# Grove_-_Mini_I2C_Motor_Driver_v1_0.net
KiCad netlist of a schematic drawn in EAGLE
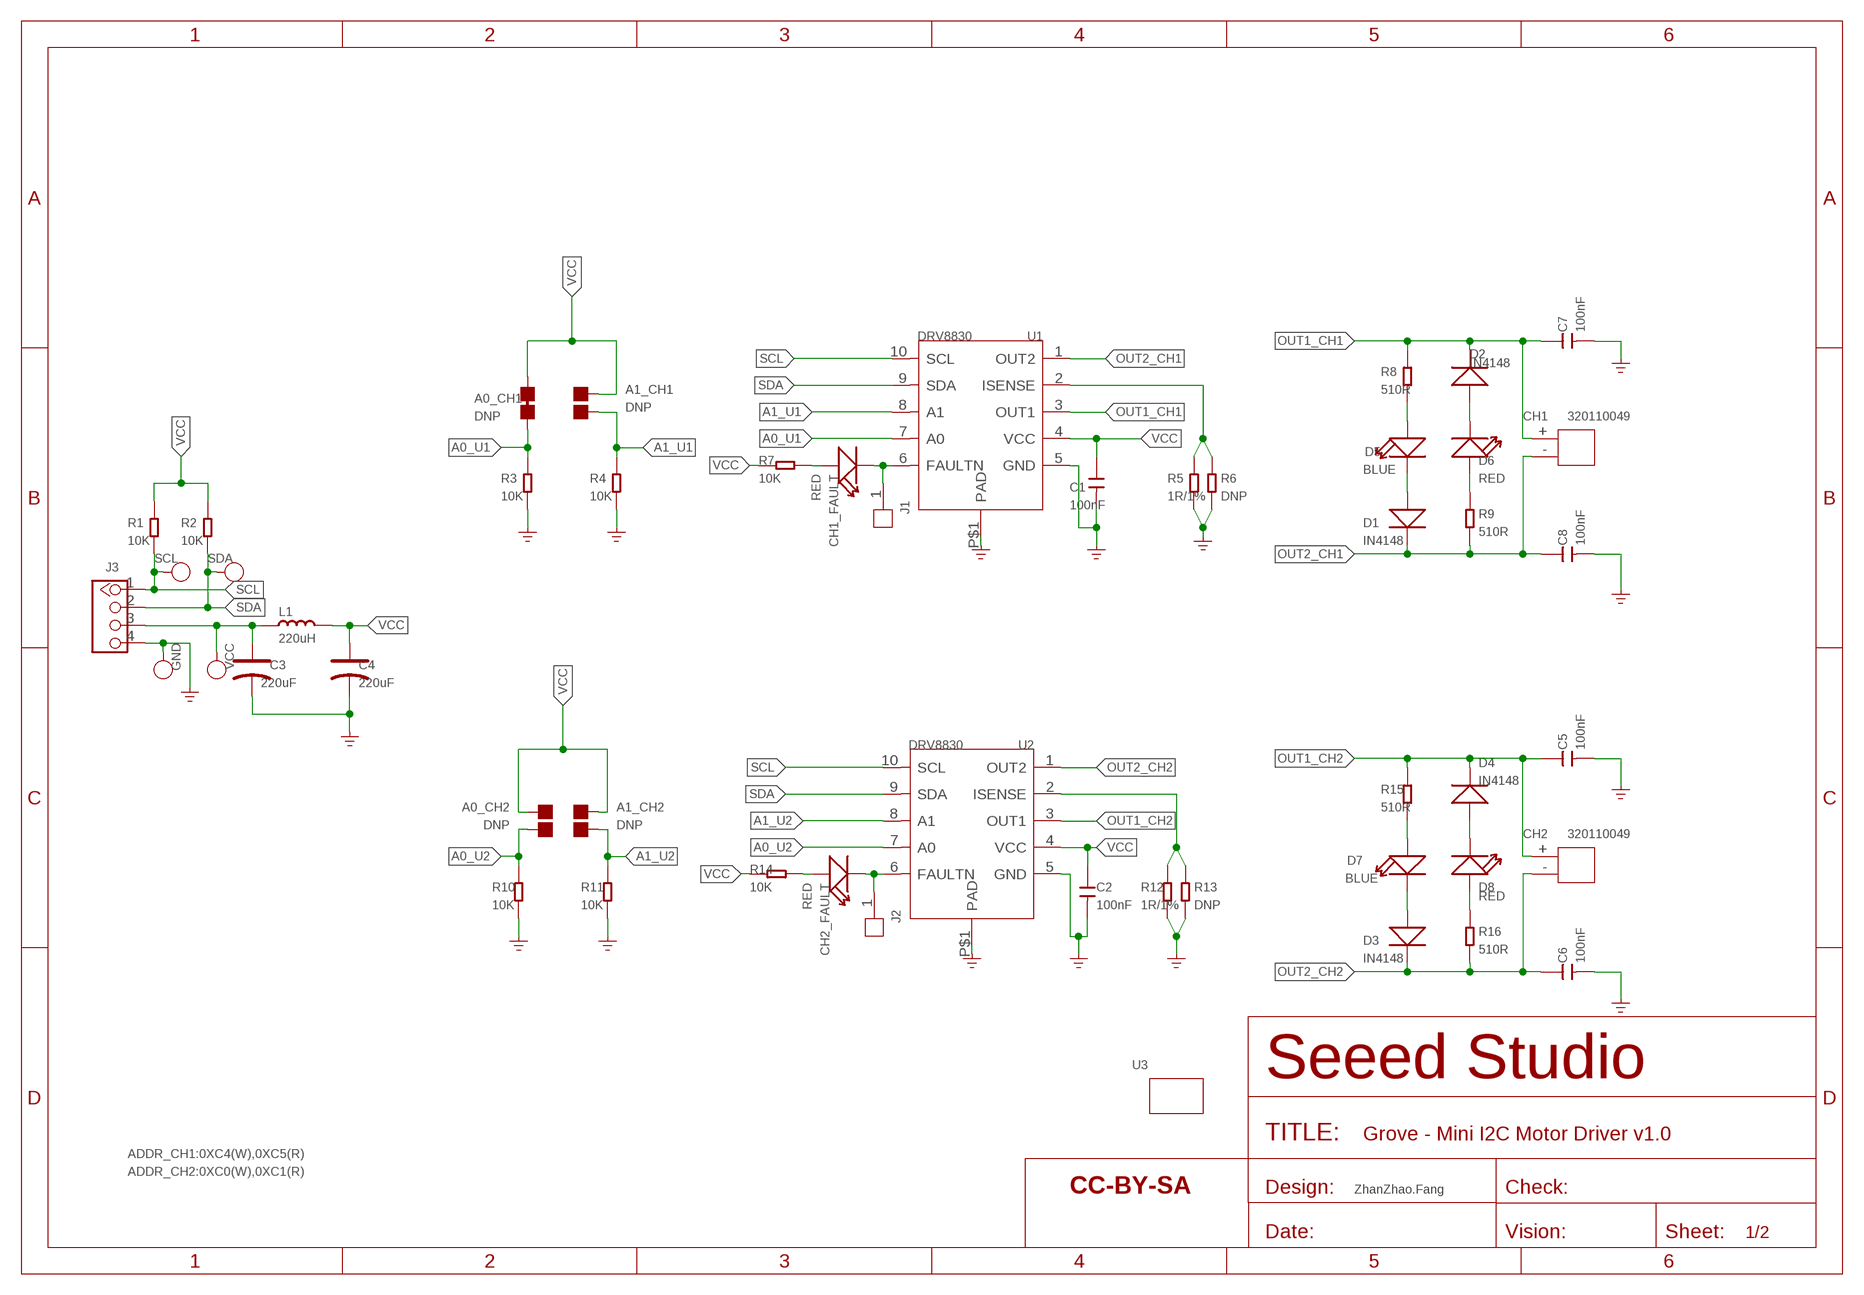
[diagram p0: schematic, sheet 1]

(export (version "E")
  (design (tool "Eeschema 10.0.6"))
  (components
    (comp (ref "A0_CH1")
      (value "DNP")
      (footprint "eagle-import:2P-SMD-SHORT")
      (libsource (lib "eagle-import") (part "JUMPER-2P-SHORT"))
    )
    (comp (ref "A0_CH2")
      (value "DNP")
      (footprint "eagle-import:JUMPER-2P")
      (libsource (lib "eagle-import") (part "JUMPER-2P"))
    )
    (comp (ref "A1_CH1")
      (value "DNP")
      (footprint "eagle-import:JUMPER-2P")
      (libsource (lib "eagle-import") (part "JUMPER-2P"))
    )
    (comp (ref "A1_CH2")
      (value "DNP")
      (footprint "eagle-import:JUMPER-2P")
      (libsource (lib "eagle-import") (part "JUMPER-2P"))
    )
    (comp (ref "C1")
      (value "100nF")
      (footprint "eagle-import:C0603")
      (libsource (lib "eagle-import") (part "CAP-0603"))
    )
    (comp (ref "C2")
      (value "100nF")
      (footprint "eagle-import:C0603")
      (libsource (lib "eagle-import") (part "CAP-0603"))
    )
    (comp (ref "C3")
      (value "220uF")
      (footprint "eagle-import:AVX-B")
      (libsource (lib "eagle-import") (part "CAP-POLAR-AVX-B"))
    )
    (comp (ref "C4")
      (value "220uF")
      (footprint "eagle-import:AVX-B")
      (libsource (lib "eagle-import") (part "CAP-POLAR-AVX-B"))
    )
    (comp (ref "C5")
      (value "100nF")
      (footprint "eagle-import:C0603")
      (libsource (lib "eagle-import") (part "CAP-0603"))
    )
    (comp (ref "C6")
      (value "100nF")
      (footprint "eagle-import:C0603")
      (libsource (lib "eagle-import") (part "CAP-0603"))
    )
    (comp (ref "C7")
      (value "100nF")
      (footprint "eagle-import:C0603")
      (libsource (lib "eagle-import") (part "CAP-0603"))
    )
    (comp (ref "C8")
      (value "100nF")
      (footprint "eagle-import:C0603")
      (libsource (lib "eagle-import") (part "CAP-0603"))
    )
    (comp (ref "CH1")
      (value "320110049")
      (footprint "eagle-import:H2-2.0-6X4.5MM")
      (libsource (lib "eagle-import") (part "JST-2P-DIP'2.0'"))
    )
    (comp (ref "CH1_FAULT")
      (value "RED")
      (footprint "eagle-import:LED-0603")
      (libsource (lib "eagle-import") (part "LED'0603'"))
    )
    (comp (ref "CH2")
      (value "320110049")
      (footprint "eagle-import:H2-2.0-6X4.5MM")
      (libsource (lib "eagle-import") (part "JST-2P-DIP'2.0'"))
    )
    (comp (ref "CH2_FAULT")
      (value "RED")
      (footprint "eagle-import:LED-0603")
      (libsource (lib "eagle-import") (part "LED'0603'"))
    )
    (comp (ref "D1")
      (value "IN4148")
      (footprint "eagle-import:SOD-323")
      (libsource (lib "eagle-import") (part "DIODE'0805'"))
    )
    (comp (ref "D2")
      (value "IN4148")
      (footprint "eagle-import:SOD-323")
      (libsource (lib "eagle-import") (part "DIODE'0805'"))
    )
    (comp (ref "D3")
      (value "IN4148")
      (footprint "eagle-import:SOD-323")
      (libsource (lib "eagle-import") (part "DIODE'0805'"))
    )
    (comp (ref "D4")
      (value "IN4148")
      (footprint "eagle-import:SOD-323")
      (libsource (lib "eagle-import") (part "DIODE'0805'"))
    )
    (comp (ref "D5")
      (value "BLUE")
      (footprint "eagle-import:LED-0603")
      (libsource (lib "eagle-import") (part "LED'0603'"))
    )
    (comp (ref "D6")
      (value "RED")
      (footprint "eagle-import:LED-0603")
      (libsource (lib "eagle-import") (part "LED'0603'"))
    )
    (comp (ref "D7")
      (value "BLUE")
      (footprint "eagle-import:LED-0603")
      (libsource (lib "eagle-import") (part "LED'0603'"))
    )
    (comp (ref "D8")
      (value "RED")
      (footprint "eagle-import:LED-0603")
      (libsource (lib "eagle-import") (part "LED'0603'"))
    )
    (comp (ref "GND")
      (value "DNP")
      (footprint "eagle-import:TP-D45MIL")
      (libsource (lib "eagle-import") (part "TEST-POINT'4545'"))
    )
    (comp (ref "J1")
      (value "HEADER-1P-40")
      (footprint "eagle-import:1P-80_40MIL")
      (libsource (lib "eagle-import") (part "HEADER-1P-40"))
    )
    (comp (ref "J2")
      (value "HEADER-1P-40")
      (footprint "eagle-import:1P-80_40MIL")
      (libsource (lib "eagle-import") (part "HEADER-1P-40"))
    )
    (comp (ref "J3")
      (value "GROVE-CONNECTOR-DIP-2.0")
      (footprint "eagle-import:HW4-2.0")
      (libsource (lib "eagle-import") (part "GROVE-CONNECTOR-DIP-2.0"))
    )
    (comp (ref "L1")
      (value "220uH")
      (footprint "eagle-import:INT2-SMD-4.8X4.8X3MM")
      (libsource (lib "eagle-import") (part "INDUCTOR/FERRITE-BEAD"))
    )
    (comp (ref "R1")
      (value "10K")
      (footprint "eagle-import:R0603")
      (libsource (lib "eagle-import") (part "RES-0603"))
    )
    (comp (ref "R2")
      (value "10K")
      (footprint "eagle-import:R0603")
      (libsource (lib "eagle-import") (part "RES-0603"))
    )
    (comp (ref "R3")
      (value "10K")
      (footprint "eagle-import:R0603")
      (libsource (lib "eagle-import") (part "RES-0603"))
    )
    (comp (ref "R4")
      (value "10K")
      (footprint "eagle-import:R0603")
      (libsource (lib "eagle-import") (part "RES-0603"))
    )
    (comp (ref "R5")
      (value "1R/1%")
      (footprint "eagle-import:R0603")
      (libsource (lib "eagle-import") (part "RES-0603"))
    )
    (comp (ref "R6")
      (value "DNP")
      (footprint "eagle-import:R0603")
      (libsource (lib "eagle-import") (part "RES-0603"))
    )
    (comp (ref "R7")
      (value "10K")
      (footprint "eagle-import:R0603")
      (libsource (lib "eagle-import") (part "RES-0603"))
    )
    (comp (ref "R8")
      (value "510R")
      (footprint "eagle-import:R0603")
      (libsource (lib "eagle-import") (part "RES-0603"))
    )
    (comp (ref "R9")
      (value "510R")
      (footprint "eagle-import:R0603")
      (libsource (lib "eagle-import") (part "RES-0603"))
    )
    (comp (ref "R10")
      (value "10K")
      (footprint "eagle-import:R0603")
      (libsource (lib "eagle-import") (part "RES-0603"))
    )
    (comp (ref "R11")
      (value "10K")
      (footprint "eagle-import:R0603")
      (libsource (lib "eagle-import") (part "RES-0603"))
    )
    (comp (ref "R12")
      (value "1R/1%")
      (footprint "eagle-import:R0603")
      (libsource (lib "eagle-import") (part "RES-0603"))
    )
    (comp (ref "R13")
      (value "DNP")
      (footprint "eagle-import:R0603")
      (libsource (lib "eagle-import") (part "RES-0603"))
    )
    (comp (ref "R14")
      (value "10K")
      (footprint "eagle-import:R0603")
      (libsource (lib "eagle-import") (part "RES-0603"))
    )
    (comp (ref "R15")
      (value "510R")
      (footprint "eagle-import:R0603")
      (libsource (lib "eagle-import") (part "RES-0603"))
    )
    (comp (ref "R16")
      (value "510R")
      (footprint "eagle-import:R0603")
      (libsource (lib "eagle-import") (part "RES-0603"))
    )
    (comp (ref "SCL")
      (value "DNP")
      (footprint "eagle-import:TP-D45MIL")
      (libsource (lib "eagle-import") (part "TEST-POINT'4545'"))
    )
    (comp (ref "SDA")
      (value "DNP")
      (footprint "eagle-import:TP-D45MIL")
      (libsource (lib "eagle-import") (part "TEST-POINT'4545'"))
    )
    (comp (ref "U$1")
      (value "SEEEDSTUDIO-OPEN-SCH-FRAME")
      (footprint "eagle-import:SEEEDSTUDIO-PCB-FRAME")
      (libsource (lib "eagle-import") (part "SEEEDSTUDIO-OPEN-SCH-FRAME"))
    )
    (comp (ref "U1")
      (value "DRV8830")
      (footprint "eagle-import:MSOP10-0.5-3X3MM")
      (libsource (lib "eagle-import") (part "DRIVER-DRV8830"))
    )
    (comp (ref "U2")
      (value "DRV8830")
      (footprint "eagle-import:MSOP10-0.5-3X3MM")
      (libsource (lib "eagle-import") (part "DRIVER-DRV8830"))
    )
    (comp (ref "U3")
      (value "GROVE'2U'")
      (footprint "eagle-import:GROVE-1_2-TEST-PLATFORM")
      (libsource (lib "eagle-import") (part "GROVE'2U'"))
    )
    (comp (ref "VCC")
      (value "DNP")
      (footprint "eagle-import:TP-D45MIL")
      (libsource (lib "eagle-import") (part "TEST-POINT'4545'"))
    )
  )
  (nets
    (net (code "1") (name "A0_U1") (class "Default")
      (node (ref "A0_CH1") (pin "1") (pinfunction "1_1") (pintype "bidirectional"))
      (node (ref "R3") (pin "2") (pinfunction "2_2") (pintype "passive"))
      (node (ref "U1") (pin "7") (pinfunction "A0_7") (pintype "bidirectional"))
    )
    (net (code "2") (name "A0_U2") (class "Default")
      (node (ref "A0_CH2") (pin "1") (pinfunction "1_1") (pintype "bidirectional"))
      (node (ref "R10") (pin "2") (pinfunction "2_2") (pintype "passive"))
      (node (ref "U2") (pin "7") (pinfunction "A0_7") (pintype "bidirectional"))
    )
    (net (code "3") (name "A1_U1") (class "Default")
      (node (ref "A1_CH1") (pin "1") (pinfunction "1_1") (pintype "bidirectional"))
      (node (ref "R4") (pin "2") (pinfunction "2_2") (pintype "passive"))
      (node (ref "U1") (pin "8") (pinfunction "A1_8") (pintype "bidirectional"))
    )
    (net (code "4") (name "A1_U2") (class "Default")
      (node (ref "A1_CH2") (pin "1") (pinfunction "1_1") (pintype "bidirectional"))
      (node (ref "R11") (pin "2") (pinfunction "2_2") (pintype "passive"))
      (node (ref "U2") (pin "8") (pinfunction "A1_8") (pintype "bidirectional"))
    )
    (net (code "5") (name "GND") (class "Default")
      (node (ref "C1") (pin "2") (pinfunction "2_2") (pintype "passive"))
      (node (ref "C2") (pin "2") (pinfunction "2_2") (pintype "passive"))
      (node (ref "C3") (pin "-") (pinfunction "-_-") (pintype "passive"))
      (node (ref "C4") (pin "-") (pinfunction "-_-") (pintype "passive"))
      (node (ref "C5") (pin "2") (pinfunction "2_2") (pintype "passive"))
      (node (ref "C6") (pin "2") (pinfunction "2_2") (pintype "passive"))
      (node (ref "C7") (pin "2") (pinfunction "2_2") (pintype "passive"))
      (node (ref "C8") (pin "2") (pinfunction "2_2") (pintype "passive"))
      (node (ref "GND") (pin "T") (pinfunction "T_T") (pintype "bidirectional"))
      (node (ref "J3") (pin "4") (pinfunction "4_4") (pintype "bidirectional"))
      (node (ref "R10") (pin "1") (pinfunction "1_1") (pintype "passive"))
      (node (ref "R11") (pin "1") (pinfunction "1_1") (pintype "passive"))
      (node (ref "R12") (pin "1") (pinfunction "1_1") (pintype "passive"))
      (node (ref "R13") (pin "1") (pinfunction "1_1") (pintype "passive"))
      (node (ref "R3") (pin "1") (pinfunction "1_1") (pintype "passive"))
      (node (ref "R4") (pin "1") (pinfunction "1_1") (pintype "passive"))
      (node (ref "R5") (pin "1") (pinfunction "1_1") (pintype "passive"))
      (node (ref "R6") (pin "1") (pinfunction "1_1") (pintype "passive"))
      (node (ref "U1") (pin "5") (pinfunction "GND_5") (pintype "bidirectional"))
      (node (ref "U1") (pin "P$1") (pinfunction "PAD_P$1") (pintype "bidirectional"))
      (node (ref "U2") (pin "5") (pinfunction "GND_5") (pintype "bidirectional"))
      (node (ref "U2") (pin "P$1") (pinfunction "PAD_P$1") (pintype "bidirectional"))
    )
    (net (code "6") (name "Net-(C3-Pad+)") (class "Default")
      (node (ref "C3") (pin "+") (pinfunction "+_+") (pintype "passive"))
      (node (ref "J3") (pin "3") (pinfunction "3_3") (pintype "bidirectional"))
      (node (ref "L1") (pin "1") (pinfunction "1_1") (pintype "passive"))
      (node (ref "VCC") (pin "T") (pinfunction "T_T") (pintype "bidirectional"))
    )
    (net (code "7") (name "Net-(CH1_FAULT-Pad+)") (class "Default")
      (node (ref "CH1_FAULT") (pin "+") (pinfunction "+_+") (pintype "passive"))
      (node (ref "R7") (pin "1") (pinfunction "1_1") (pintype "passive"))
    )
    (net (code "8") (name "Net-(CH2_FAULT-Pad+)") (class "Default")
      (node (ref "CH2_FAULT") (pin "+") (pinfunction "+_+") (pintype "passive"))
      (node (ref "R14") (pin "1") (pinfunction "1_1") (pintype "passive"))
    )
    (net (code "9") (name "Net-(D1-Pad+)") (class "Default")
      (node (ref "D1") (pin "+") (pinfunction "+_+") (pintype "passive"))
      (node (ref "D5") (pin "-") (pinfunction "-_-") (pintype "passive"))
    )
    (net (code "10") (name "Net-(D2-Pad+)") (class "Default")
      (node (ref "D2") (pin "+") (pinfunction "+_+") (pintype "passive"))
      (node (ref "D6") (pin "-") (pinfunction "-_-") (pintype "passive"))
    )
    (net (code "11") (name "Net-(D3-Pad+)") (class "Default")
      (node (ref "D3") (pin "+") (pinfunction "+_+") (pintype "passive"))
      (node (ref "D7") (pin "-") (pinfunction "-_-") (pintype "passive"))
    )
    (net (code "12") (name "Net-(D4-Pad+)") (class "Default")
      (node (ref "D4") (pin "+") (pinfunction "+_+") (pintype "passive"))
      (node (ref "D8") (pin "-") (pinfunction "-_-") (pintype "passive"))
    )
    (net (code "13") (name "Net-(D5-Pad+)") (class "Default")
      (node (ref "D5") (pin "+") (pinfunction "+_+") (pintype "passive"))
      (node (ref "R8") (pin "1") (pinfunction "1_1") (pintype "passive"))
    )
    (net (code "14") (name "Net-(D6-Pad+)") (class "Default")
      (node (ref "D6") (pin "+") (pinfunction "+_+") (pintype "passive"))
      (node (ref "R9") (pin "2") (pinfunction "2_2") (pintype "passive"))
    )
    (net (code "15") (name "Net-(D7-Pad+)") (class "Default")
      (node (ref "D7") (pin "+") (pinfunction "+_+") (pintype "passive"))
      (node (ref "R15") (pin "1") (pinfunction "1_1") (pintype "passive"))
    )
    (net (code "16") (name "Net-(D8-Pad+)") (class "Default")
      (node (ref "D8") (pin "+") (pinfunction "+_+") (pintype "passive"))
      (node (ref "R16") (pin "2") (pinfunction "2_2") (pintype "passive"))
    )
    (net (code "17") (name "Net-(U1-FAULTN)") (class "Default")
      (node (ref "CH1_FAULT") (pin "-") (pinfunction "-_-") (pintype "passive"))
      (node (ref "J1") (pin "1") (pinfunction "1_1") (pintype "bidirectional"))
      (node (ref "U1") (pin "6") (pinfunction "FAULTN_6") (pintype "bidirectional"))
    )
    (net (code "18") (name "Net-(U1-ISENSE)") (class "Default")
      (node (ref "R5") (pin "2") (pinfunction "2_2") (pintype "passive"))
      (node (ref "R6") (pin "2") (pinfunction "2_2") (pintype "passive"))
      (node (ref "U1") (pin "2") (pinfunction "ISENSE_2") (pintype "bidirectional"))
    )
    (net (code "19") (name "Net-(U2-FAULTN)") (class "Default")
      (node (ref "CH2_FAULT") (pin "-") (pinfunction "-_-") (pintype "passive"))
      (node (ref "J2") (pin "1") (pinfunction "1_1") (pintype "bidirectional"))
      (node (ref "U2") (pin "6") (pinfunction "FAULTN_6") (pintype "bidirectional"))
    )
    (net (code "20") (name "Net-(U2-ISENSE)") (class "Default")
      (node (ref "R12") (pin "2") (pinfunction "2_2") (pintype "passive"))
      (node (ref "R13") (pin "2") (pinfunction "2_2") (pintype "passive"))
      (node (ref "U2") (pin "2") (pinfunction "ISENSE_2") (pintype "bidirectional"))
    )
    (net (code "21") (name "OUT1_CH1") (class "Default")
      (node (ref "C7") (pin "1") (pinfunction "1_1") (pintype "passive"))
      (node (ref "CH1") (pin "+") (pinfunction "P$1_+") (pintype "bidirectional"))
      (node (ref "D2") (pin "-") (pinfunction "-_-") (pintype "passive"))
      (node (ref "R8") (pin "2") (pinfunction "2_2") (pintype "passive"))
      (node (ref "U1") (pin "3") (pinfunction "OUT1_3") (pintype "bidirectional"))
    )
    (net (code "22") (name "OUT1_CH2") (class "Default")
      (node (ref "C5") (pin "1") (pinfunction "1_1") (pintype "passive"))
      (node (ref "CH2") (pin "+") (pinfunction "P$1_+") (pintype "bidirectional"))
      (node (ref "D4") (pin "-") (pinfunction "-_-") (pintype "passive"))
      (node (ref "R15") (pin "2") (pinfunction "2_2") (pintype "passive"))
      (node (ref "U2") (pin "3") (pinfunction "OUT1_3") (pintype "bidirectional"))
    )
    (net (code "23") (name "OUT2_CH1") (class "Default")
      (node (ref "C8") (pin "1") (pinfunction "1_1") (pintype "passive"))
      (node (ref "CH1") (pin "-") (pinfunction "P$2_-") (pintype "bidirectional"))
      (node (ref "D1") (pin "-") (pinfunction "-_-") (pintype "passive"))
      (node (ref "R9") (pin "1") (pinfunction "1_1") (pintype "passive"))
      (node (ref "U1") (pin "1") (pinfunction "OUT2_1") (pintype "bidirectional"))
    )
    (net (code "24") (name "OUT2_CH2") (class "Default")
      (node (ref "C6") (pin "1") (pinfunction "1_1") (pintype "passive"))
      (node (ref "CH2") (pin "-") (pinfunction "P$2_-") (pintype "bidirectional"))
      (node (ref "D3") (pin "-") (pinfunction "-_-") (pintype "passive"))
      (node (ref "R16") (pin "1") (pinfunction "1_1") (pintype "passive"))
      (node (ref "U2") (pin "1") (pinfunction "OUT2_1") (pintype "bidirectional"))
    )
    (net (code "25") (name "SCL") (class "Default")
      (node (ref "J3") (pin "1") (pinfunction "1_1") (pintype "bidirectional"))
      (node (ref "R1") (pin "1") (pinfunction "1_1") (pintype "passive"))
      (node (ref "SCL") (pin "T") (pinfunction "T_T") (pintype "bidirectional"))
      (node (ref "U1") (pin "10") (pinfunction "SCL_10") (pintype "bidirectional"))
      (node (ref "U2") (pin "10") (pinfunction "SCL_10") (pintype "bidirectional"))
    )
    (net (code "26") (name "SDA") (class "Default")
      (node (ref "J3") (pin "2") (pinfunction "2_2") (pintype "bidirectional"))
      (node (ref "R2") (pin "1") (pinfunction "1_1") (pintype "passive"))
      (node (ref "SDA") (pin "T") (pinfunction "T_T") (pintype "bidirectional"))
      (node (ref "U1") (pin "9") (pinfunction "SDA_9") (pintype "bidirectional"))
      (node (ref "U2") (pin "9") (pinfunction "SDA_9") (pintype "bidirectional"))
    )
    (net (code "27") (name "VCC") (class "Default")
      (node (ref "A0_CH1") (pin "2") (pinfunction "2_2") (pintype "bidirectional"))
      (node (ref "A0_CH2") (pin "2") (pinfunction "2_2") (pintype "bidirectional"))
      (node (ref "A1_CH1") (pin "2") (pinfunction "2_2") (pintype "bidirectional"))
      (node (ref "A1_CH2") (pin "2") (pinfunction "2_2") (pintype "bidirectional"))
      (node (ref "C1") (pin "1") (pinfunction "1_1") (pintype "passive"))
      (node (ref "C2") (pin "1") (pinfunction "1_1") (pintype "passive"))
      (node (ref "C4") (pin "+") (pinfunction "+_+") (pintype "passive"))
      (node (ref "L1") (pin "2") (pinfunction "2_2") (pintype "passive"))
      (node (ref "R1") (pin "2") (pinfunction "2_2") (pintype "passive"))
      (node (ref "R14") (pin "2") (pinfunction "2_2") (pintype "passive"))
      (node (ref "R2") (pin "2") (pinfunction "2_2") (pintype "passive"))
      (node (ref "R7") (pin "2") (pinfunction "2_2") (pintype "passive"))
      (node (ref "U1") (pin "4") (pinfunction "VCC_4") (pintype "bidirectional"))
      (node (ref "U2") (pin "4") (pinfunction "VCC_4") (pintype "bidirectional"))
    )
  )
)
